# EASYEDA_SCHEMA.net
KiCad netlist of a schematic drawn in EasyEDA
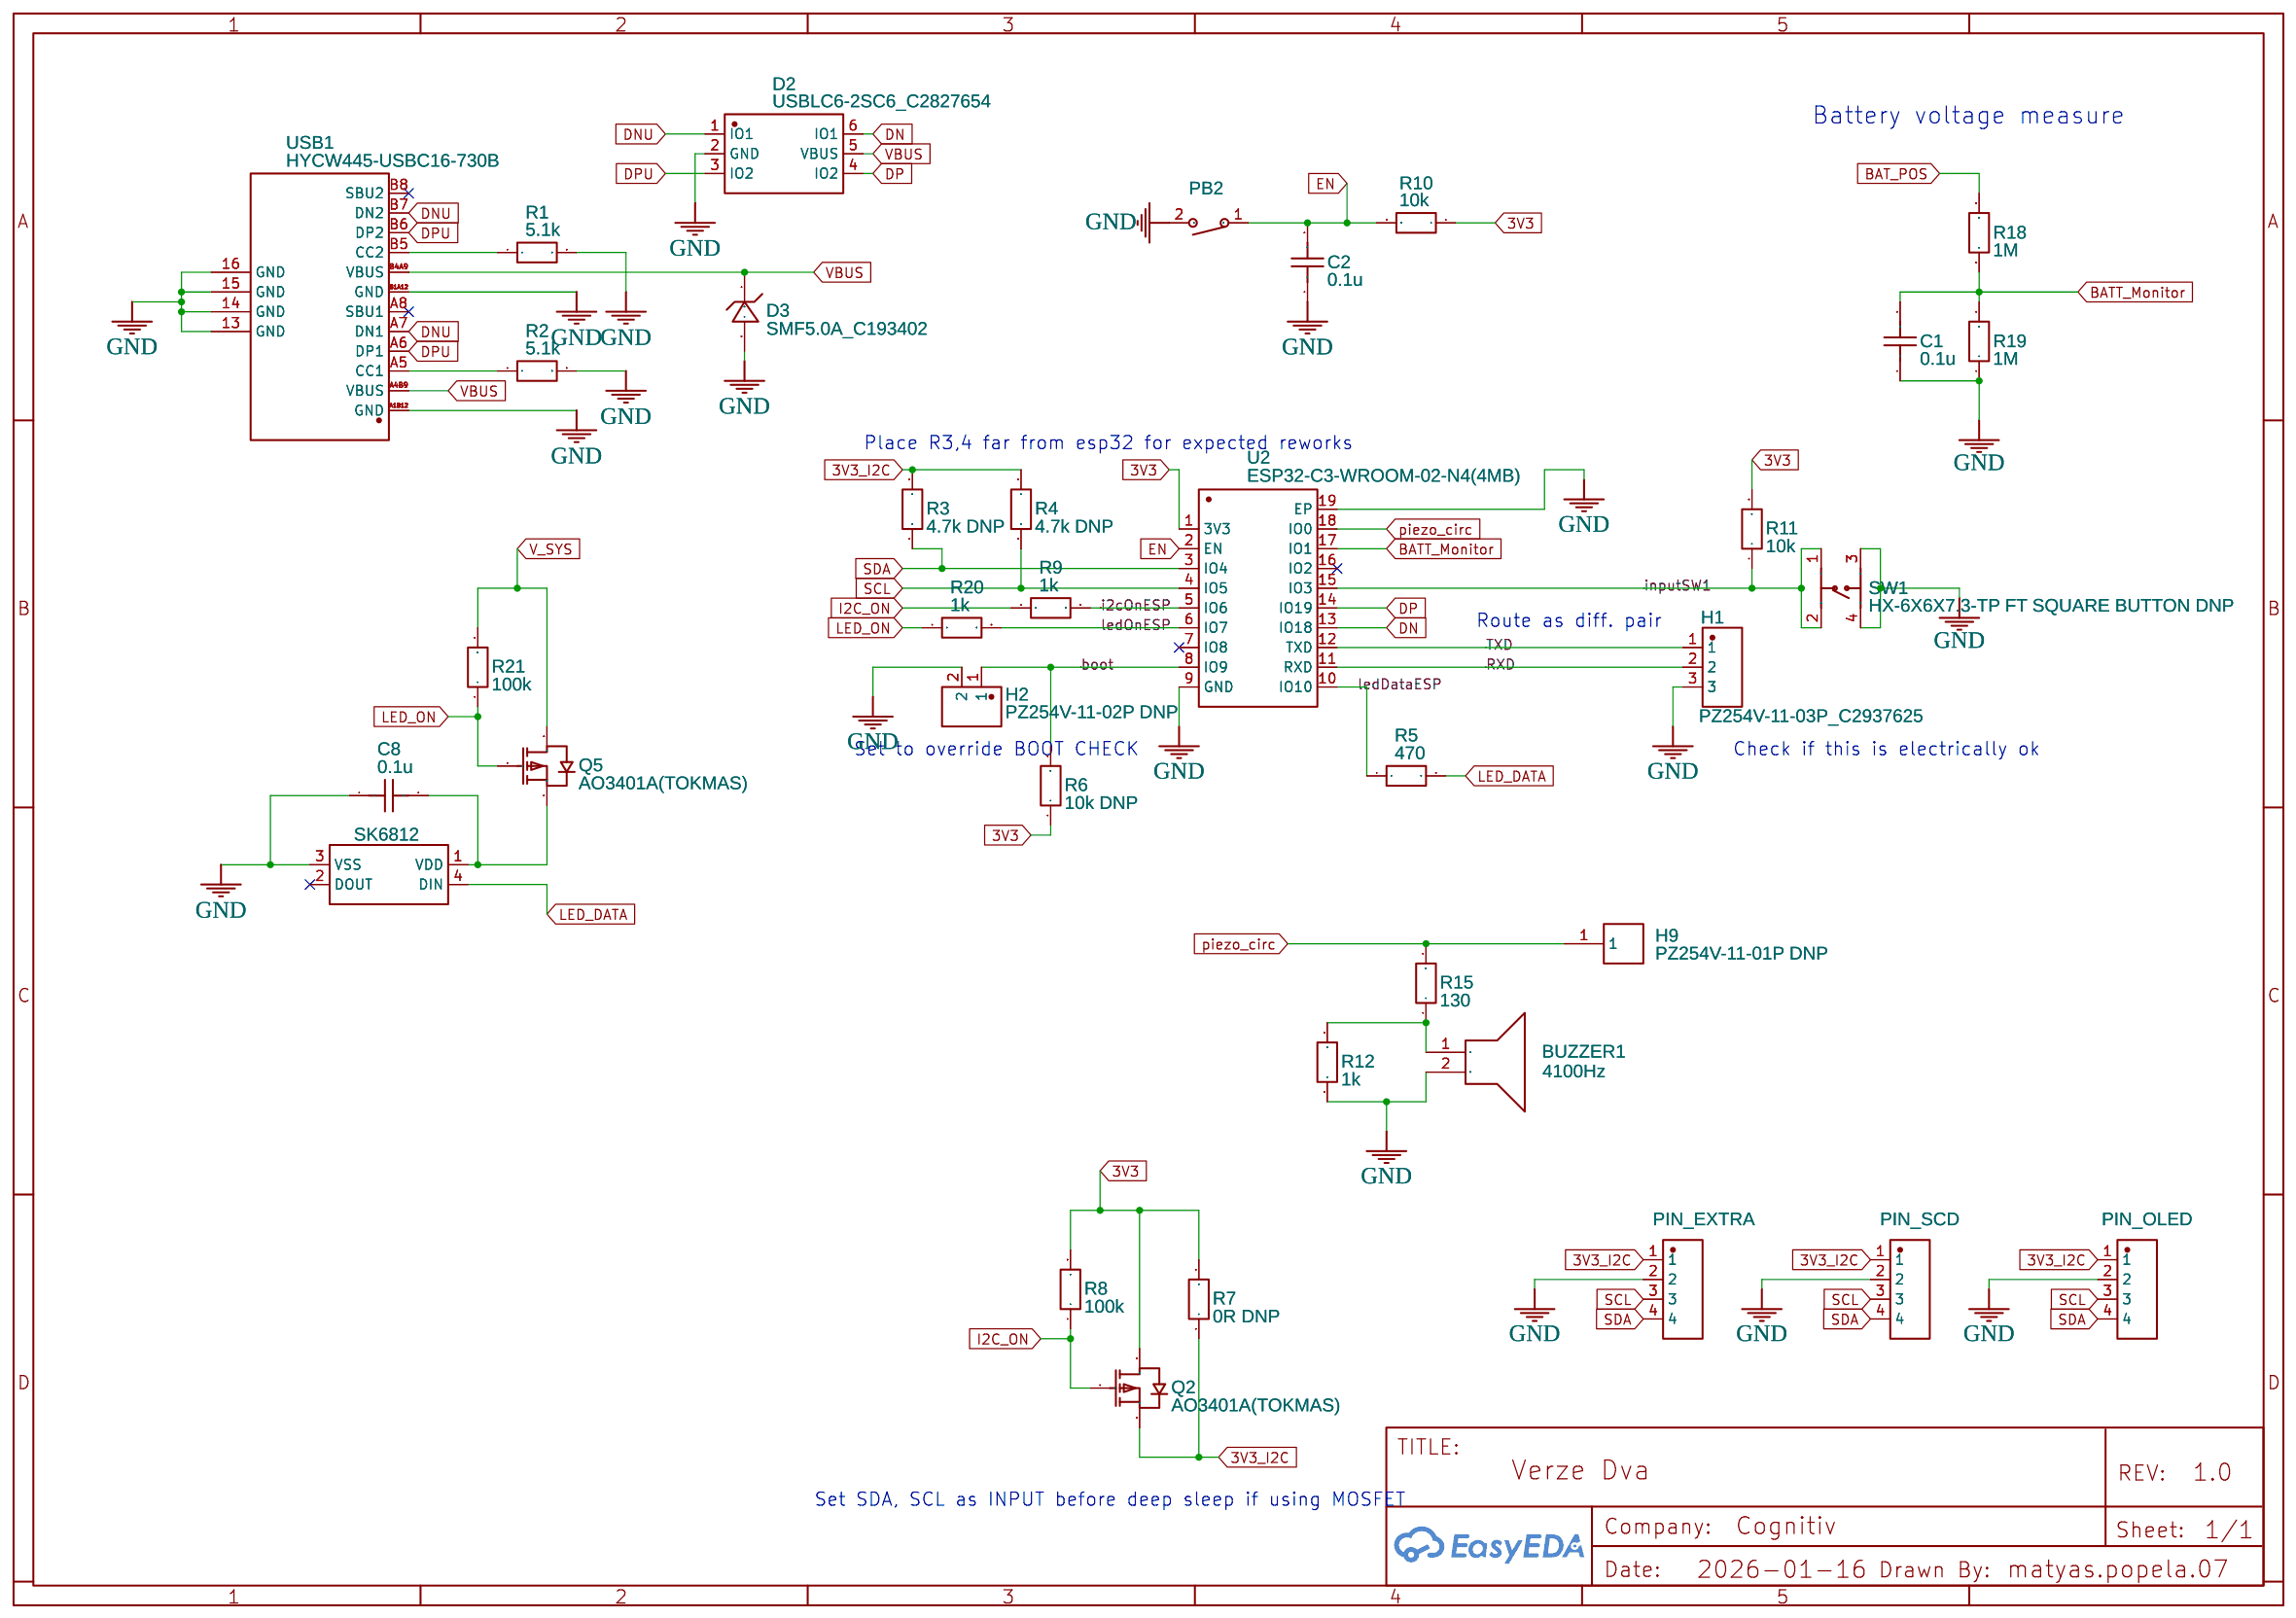
[diagram p0: Mainboard_C3]
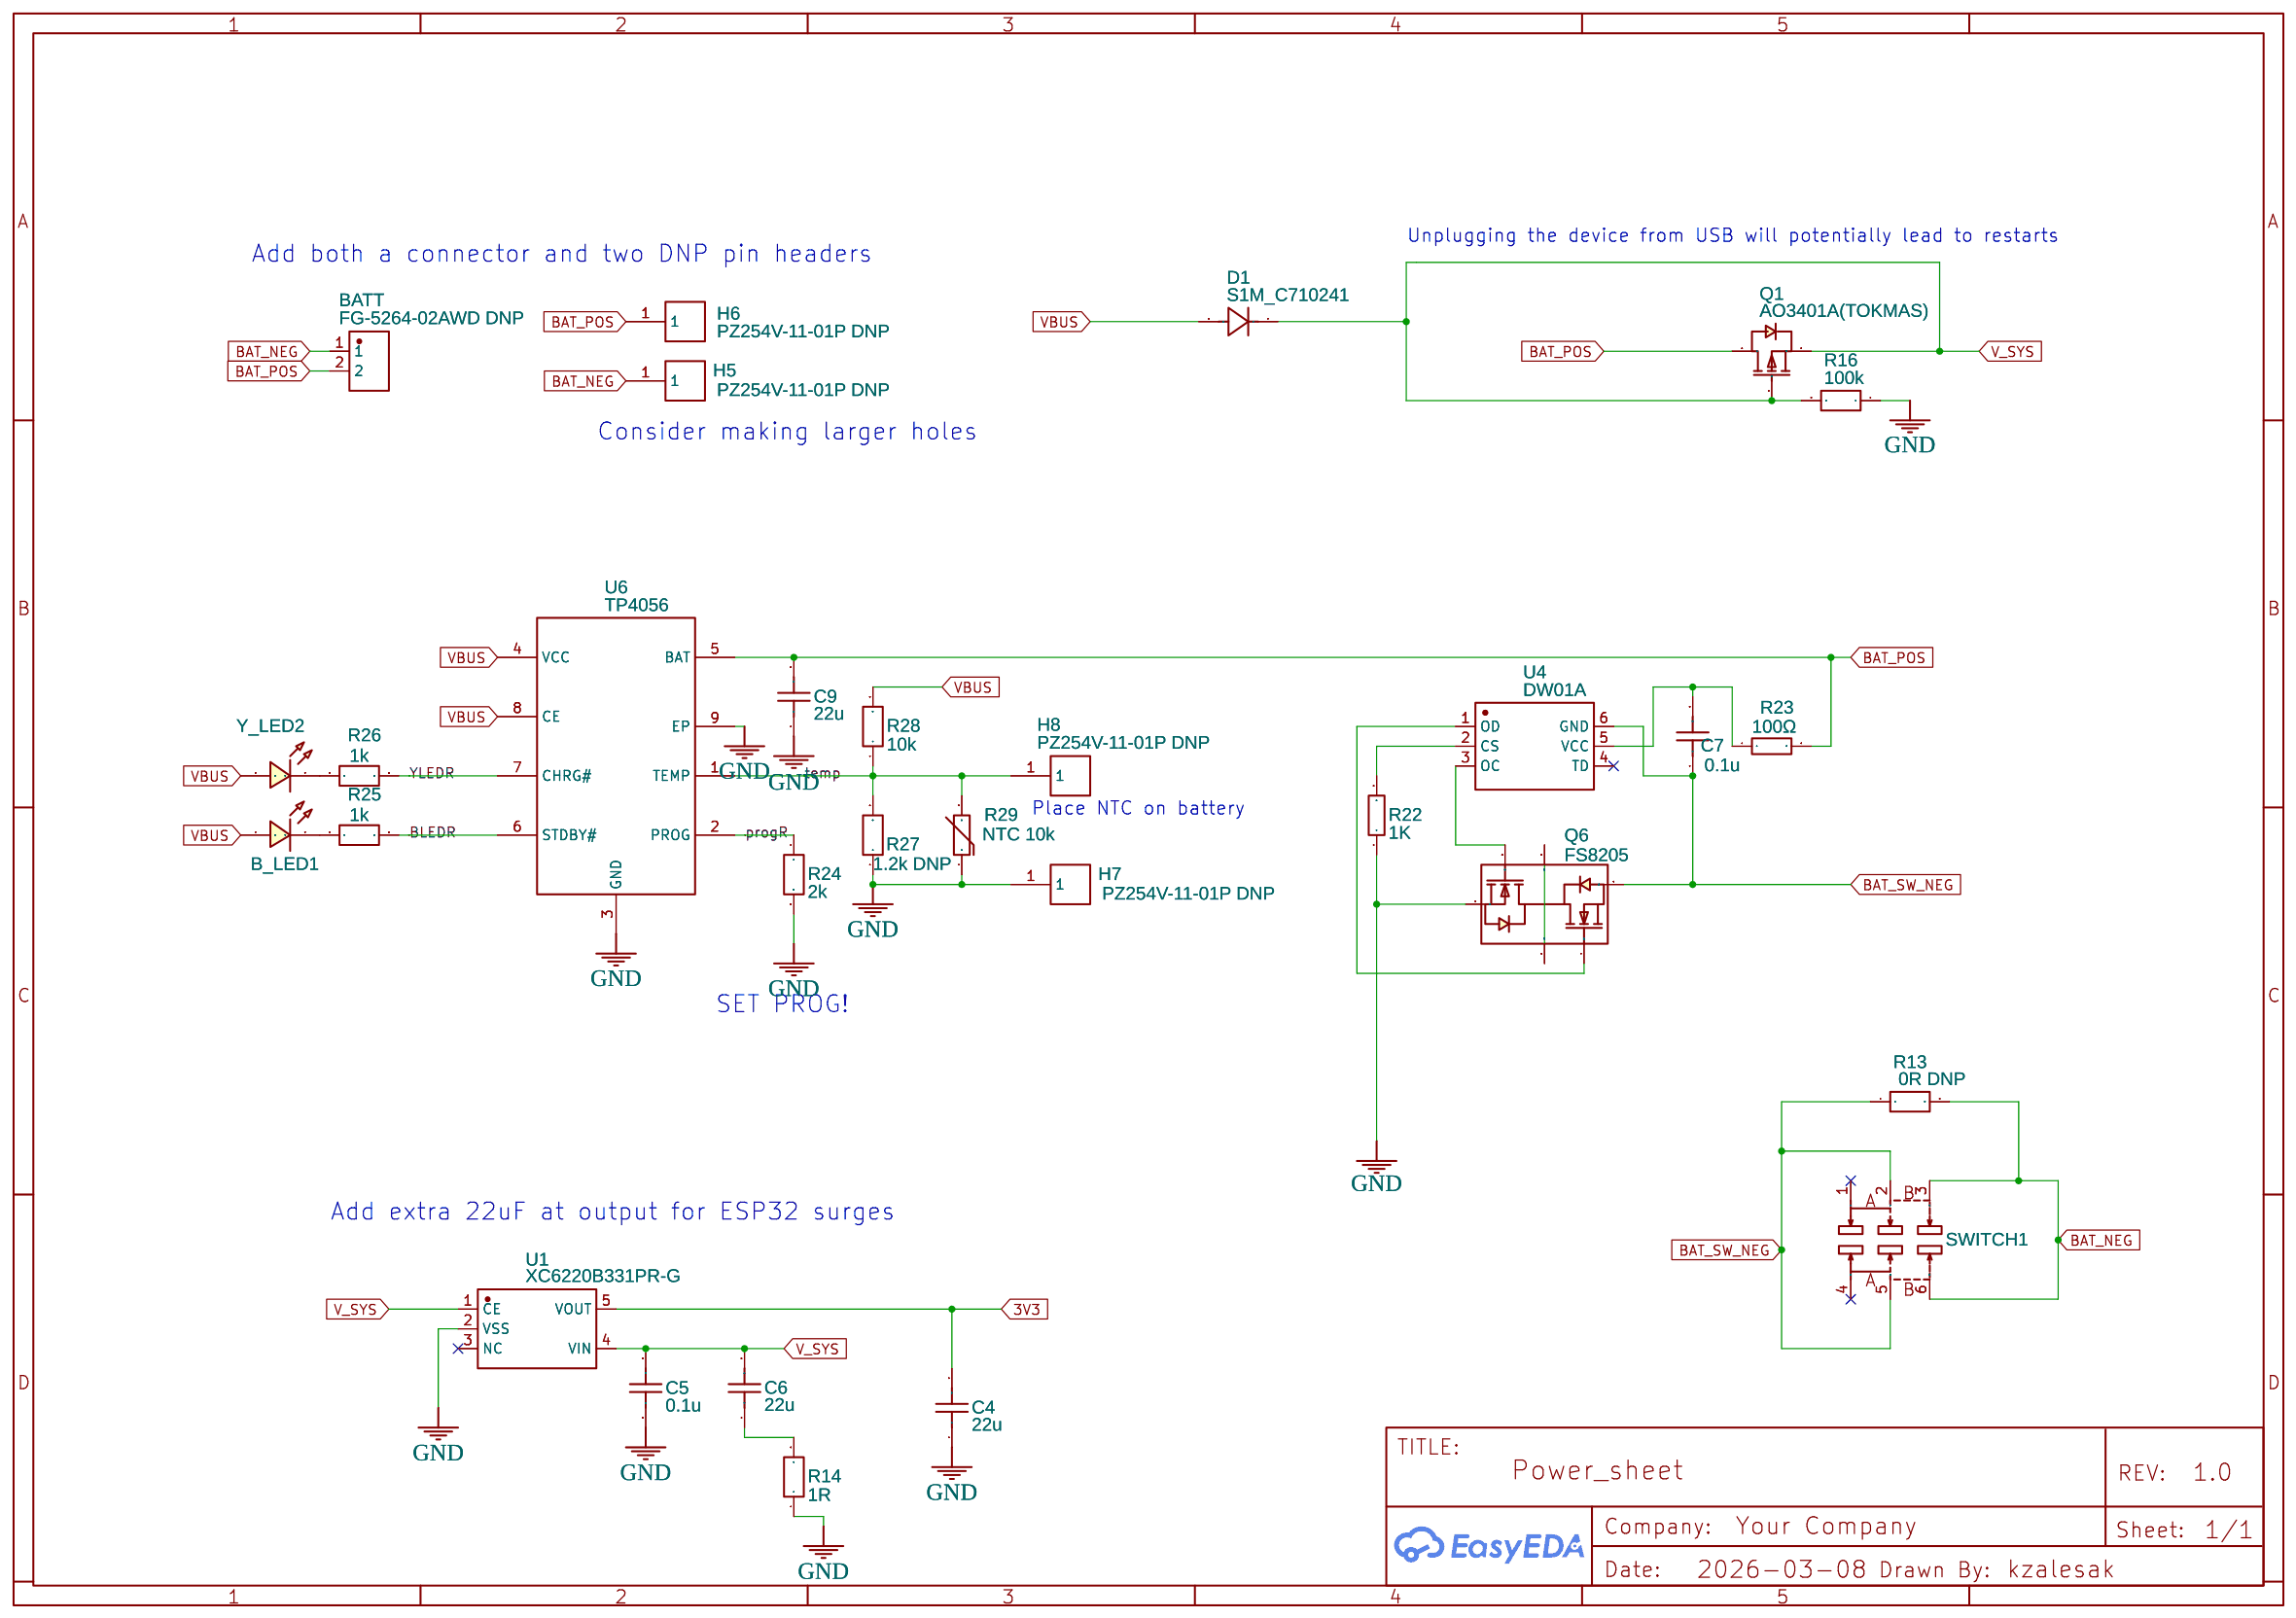
[diagram p1: Power_Management]

(export (version "E")
  (design (tool "Eeschema 10.0.6"))
  (components
    (comp (ref "BUZZER1")
      (value "4100Hz")
      (fields (field (name "Manufacturer Part") "FUET-1109") (field (name "Manufacturer") "FUET(福声科技)"))
      (libsource (lib "") (part "FST-1109"))
    )
    (comp (ref "C1")
      (value "0.1u")
      (fields
        (field (name "Manufacturer Part") "CC0603KRX7R9BB104")
        (field (name "Manufacturer") "YAGEO(国巨)")
      )
      (libsource (lib "") (part "C_0603_US"))
    )
    (comp (ref "C2")
      (value "0.1u")
      (fields
        (field (name "Manufacturer Part") "CC0603KRX7R9BB104")
        (field (name "Manufacturer") "YAGEO(国巨)")
      )
      (libsource (lib "") (part "C_0603_US"))
    )
    (comp (ref "C8")
      (value "0.1u")
      (fields
        (field (name "Manufacturer Part") "CC0603KRX7R9BB104")
        (field (name "Manufacturer") "YAGEO(国巨)")
      )
      (libsource (lib "") (part "C_0603_US_1"))
    )
    (comp (ref "D2")
      (value "USBLC6-2SC6_C2827654")
      (fields
        (field (name "Manufacturer Part") "USBLC6-2SC6")
        (field (name "Manufacturer") "TECH PUBLIC(台舟)")
      )
      (libsource (lib "") (part "USBLC6-2SC6_C2827654"))
    )
    (comp (ref "D3")
      (value "SMF5.0A_C193402")
      (fields (field (name "Manufacturer Part") "SMF5.0A") (field (name "Manufacturer") "MDD(辰达半导体)"))
      (libsource (lib "") (part "SMF5.0A_C193402"))
    )
    (comp (ref "H1")
      (value "PZ254V-11-03P_C2937625")
      (fields (field (name "Manufacturer Part") "PZ254V-11-03P") (field (name "Manufacturer") "XFCN(兴飞)"))
      (libsource (lib "") (part "PZ254V-11-03P_C2937625"))
    )
    (comp (ref "H2")
      (value "PZ254V-11-02P DNP")
      (fields (field (name "Manufacturer Part") "PZ254V-11-02P") (field (name "Manufacturer") "XFCN(兴飞)"))
      (libsource (lib "") (part "PZ254V-11-02P"))
    )
    (comp (ref "H9")
      (value "PZ254V-11-01P DNP")
      (fields (field (name "Manufacturer Part") "PZ254V-11-01P") (field (name "Manufacturer") "XFCN(兴飞)"))
      (libsource (lib "") (part "PZ254V-11-01P"))
    )
    (comp (ref "PB2")
      (value "HX 3X4X2-2P-1.6N TACTILE SWITCH DNP")
      (fields
        (field (name "Manufacturer Part") "HX 3x4x2-2P-1.6N TACTILE SWITCH")
        (field (name "Manufacturer") "hanxia(韩下)")
      )
      (libsource (lib "") (part "HX 3X4X2-2P-1.6N TACTILE SWITCH"))
    )
    (comp (ref "PIN_EXTRA")
      (value "2.54-1*4")
      (fields (field (name "Manufacturer") "ZHOURI(洲日)"))
      (libsource (lib "") (part "2.54-1*4"))
    )
    (comp (ref "PIN_OLED")
      (value "2.54-1*4")
      (fields (field (name "Manufacturer") "ZHOURI(洲日)"))
      (libsource (lib "") (part "2.54-1*4_2"))
    )
    (comp (ref "PIN_SCD")
      (value "2.54-1*4")
      (fields (field (name "Manufacturer") "ZHOURI(洲日)"))
      (libsource (lib "") (part "2.54-1*4_1"))
    )
    (comp (ref "Q2")
      (value "AO3401A(TOKMAS)")
      (fields (field (name "Manufacturer") "Tokmas(托克马斯)"))
      (libsource (lib "") (part "AO3401A(TOKMAS)"))
    )
    (comp (ref "Q5")
      (value "AO3401A(TOKMAS)")
      (fields (field (name "Manufacturer") "Tokmas(托克马斯)"))
      (libsource (lib "") (part "AO3401A(TOKMAS)"))
    )
    (comp (ref "R1")
      (value "5.1k")
      (fields
        (field (name "Manufacturer Part") "0603WAF5101T5E")
        (field (name "Manufacturer") "UNI-ROYAL(厚声)")
      )
      (libsource (lib "") (part "R_0603_EU"))
    )
    (comp (ref "R2")
      (value "5.1k")
      (fields
        (field (name "Manufacturer Part") "0603WAF5101T5E")
        (field (name "Manufacturer") "UNI-ROYAL(厚声)")
      )
      (libsource (lib "") (part "R_0603_EU"))
    )
    (comp (ref "R3")
      (value "4.7k DNP")
      (fields
        (field (name "Manufacturer Part") "0603WAF4701T5E")
        (field (name "Manufacturer") "UNI-ROYAL(厚声)")
      )
      (libsource (lib "") (part "R_0603_EU_2"))
    )
    (comp (ref "R4")
      (value "4.7k DNP")
      (fields
        (field (name "Manufacturer Part") "0603WAF4701T5E")
        (field (name "Manufacturer") "UNI-ROYAL(厚声)")
      )
      (libsource (lib "") (part "R_0603_EU_2"))
    )
    (comp (ref "R5")
      (value "470")
      (fields
        (field (name "Manufacturer Part") "0603WAF4700T5E")
        (field (name "Manufacturer") "UNI-ROYAL(厚声)")
      )
      (libsource (lib "") (part "R_0603_EU"))
    )
    (comp (ref "R6")
      (value "10k DNP")
      (fields
        (field (name "Manufacturer Part") "0603WAF1002T5E")
        (field (name "Manufacturer") "UNI-ROYAL(厚声)")
      )
      (libsource (lib "") (part "R_0603_EU_2"))
    )
    (comp (ref "R7")
      (value "0R DNP")
      (fields
        (field (name "Manufacturer Part") "0603WAF0000T5E")
        (field (name "Manufacturer") "UNI-ROYAL(厚声)")
      )
      (libsource (lib "") (part "R_0603_EU_2"))
    )
    (comp (ref "R8")
      (value "100k")
      (fields
        (field (name "Manufacturer Part") "0603WAF1003T5E")
        (field (name "Manufacturer") "UNI-ROYAL(厚声)")
      )
      (libsource (lib "") (part "R_0603_EU_2"))
    )
    (comp (ref "R9")
      (value "1k")
      (fields
        (field (name "Manufacturer Part") "0603WAF1001T5E")
        (field (name "Manufacturer") "UNI-ROYAL(厚声)")
      )
      (libsource (lib "") (part "R_0603_EU"))
    )
    (comp (ref "R10")
      (value "10k")
      (fields
        (field (name "Manufacturer Part") "0603WAF1002T5E")
        (field (name "Manufacturer") "UNI-ROYAL(厚声)")
      )
      (libsource (lib "") (part "R_0603_EU_1"))
    )
    (comp (ref "R11")
      (value "10k")
      (fields
        (field (name "Manufacturer Part") "0603WAF1002T5E")
        (field (name "Manufacturer") "UNI-ROYAL(厚声)")
      )
      (libsource (lib "") (part "R_0603_EU_2"))
    )
    (comp (ref "R12")
      (value "1k")
      (fields
        (field (name "Manufacturer Part") "0603WAF1001T5E")
        (field (name "Manufacturer") "UNI-ROYAL(厚声)")
      )
      (libsource (lib "") (part "R_0603_EU_2"))
    )
    (comp (ref "R15")
      (value "130")
      (fields
        (field (name "Manufacturer Part") "0603WAF1200T5E")
        (field (name "Manufacturer") "UNI-ROYAL(厚声)")
      )
      (libsource (lib "") (part "R_0603_EU_2"))
    )
    (comp (ref "R18")
      (value "1M")
      (fields
        (field (name "Manufacturer Part") "0603WAF1004T5E")
        (field (name "Manufacturer") "UNI-ROYAL(厚声)")
      )
      (libsource (lib "") (part "R_0603_EU_2"))
    )
    (comp (ref "R19")
      (value "1M")
      (fields
        (field (name "Manufacturer Part") "0603WAF1004T5E")
        (field (name "Manufacturer") "UNI-ROYAL(厚声)")
      )
      (libsource (lib "") (part "R_0603_EU_2"))
    )
    (comp (ref "R20")
      (value "1k")
      (fields
        (field (name "Manufacturer Part") "0603WAF1001T5E")
        (field (name "Manufacturer") "UNI-ROYAL(厚声)")
      )
      (libsource (lib "") (part "R_0603_EU"))
    )
    (comp (ref "R21")
      (value "100k")
      (fields
        (field (name "Manufacturer Part") "0603WAF1003T5E")
        (field (name "Manufacturer") "UNI-ROYAL(厚声)")
      )
      (libsource (lib "") (part "R_0603_EU_2"))
    )
    (comp (ref "SK6812")
      (value "SK6812_C5378720")
      (fields (field (name "Manufacturer Part") "SK6812") (field (name "Manufacturer") "欧思科光电"))
      (libsource (lib "") (part "SK6812_C5378720"))
    )
    (comp (ref "SW1")
      (value "HX-6X6X7.3-TP FT SQUARE BUTTON DNP")
      (fields
        (field (name "Manufacturer Part") "HX-6x6x7.3-TP FT square button")
        (field (name "Manufacturer") "hanxia(韩下)")
      )
      (libsource (lib "") (part "HX-6X6X7.3-TP FT SQUARE BUTTON"))
    )
    (comp (ref "U2")
      (value "ESP32-C3-WROOM-02-N4(4MB)")
      (fields
        (field (name "Manufacturer Part") "ESP32-C3-WROOM-02-N4")
        (field (name "Manufacturer") "ESPRESSIF(乐鑫)")
      )
      (libsource (lib "") (part "ESP32-C3-WROOM-02-N4(4MB)"))
    )
    (comp (ref "USB1")
      (value "HYCW445-USBC16-730B")
      (fields (field (name "Manufacturer") "华宇创"))
      (libsource (lib "") (part "HYCW445-USBC16-730B"))
    )
    (comp (ref "BATT")
      (value "FG-5264-02AWD DNP")
      (fields (field (name "Manufacturer Part") "FG-5264-02AWD") (field (name "Manufacturer") "FG(富港)"))
      (libsource (lib "") (part "FG-5264-02AWD"))
    )
    (comp (ref "B_LED1")
      (value "LED-0603_R")
      (fields
        (field (name "Manufacturer Part") "19-217/R6C-AL1M2VY/3T")
        (field (name "Manufacturer") "EVERLIGHT(台湾亿光)")
      )
      (libsource (lib "") (part "LED-0603_R"))
    )
    (comp (ref "C4")
      (value "22u")
      (fields
        (field (name "Manufacturer Part") "CL21A226MAQNNNE")
        (field (name "Manufacturer") "SAMSUNG(三星)")
      )
      (libsource (lib "") (part "CL21A226MAQNNNE"))
    )
    (comp (ref "C5")
      (value "0.1u")
      (fields
        (field (name "Manufacturer Part") "CC0603KRX7R9BB104")
        (field (name "Manufacturer") "YAGEO(国巨)")
      )
      (libsource (lib "") (part "C_0603_US"))
    )
    (comp (ref "C6")
      (value "22u")
      (fields
        (field (name "Manufacturer Part") "CL21A226MAQNNNE")
        (field (name "Manufacturer") "SAMSUNG(三星)")
      )
      (libsource (lib "") (part "CL21A226MAQNNNE"))
    )
    (comp (ref "C7")
      (value "0.1u")
      (fields
        (field (name "Manufacturer Part") "CC0603KRX7R9BB104")
        (field (name "Manufacturer") "YAGEO(国巨)")
      )
      (libsource (lib "") (part "C_0603_US"))
    )
    (comp (ref "C9")
      (value "22u")
      (fields
        (field (name "Manufacturer Part") "CL21A226MAQNNNE")
        (field (name "Manufacturer") "SAMSUNG(三星)")
      )
      (libsource (lib "") (part "CL21A226MAQNNNE"))
    )
    (comp (ref "D1")
      (value "S1M_C710241")
      (fields (field (name "Manufacturer Part") "S1M") (field (name "Manufacturer") "DIODES(美台)"))
      (libsource (lib "") (part "S1M_C710241"))
    )
    (comp (ref "H5")
      (value "PZ254V-11-01P DNP")
      (fields (field (name "Manufacturer Part") "PZ254V-11-01P") (field (name "Manufacturer") "XFCN(兴飞)"))
      (libsource (lib "") (part "PZ254V-11-01P"))
    )
    (comp (ref "H6")
      (value "PZ254V-11-01P DNP")
      (fields (field (name "Manufacturer Part") "PZ254V-11-01P") (field (name "Manufacturer") "XFCN(兴飞)"))
      (libsource (lib "") (part "PZ254V-11-01P"))
    )
    (comp (ref "H7")
      (value "PZ254V-11-01P DNP")
      (fields (field (name "Manufacturer Part") "PZ254V-11-01P") (field (name "Manufacturer") "XFCN(兴飞)"))
      (libsource (lib "") (part "PZ254V-11-01P"))
    )
    (comp (ref "H8")
      (value "PZ254V-11-01P DNP")
      (fields (field (name "Manufacturer Part") "PZ254V-11-01P") (field (name "Manufacturer") "XFCN(兴飞)"))
      (libsource (lib "") (part "PZ254V-11-01P"))
    )
    (comp (ref "Q1")
      (value "AO3401A(TOKMAS)")
      (fields (field (name "Manufacturer") "Tokmas(托克马斯)"))
      (libsource (lib "") (part "AO3401A(TOKMAS)"))
    )
    (comp (ref "Q6")
      (value "FS8205")
      (fields (field (name "Manufacturer") "FORTUNE"))
      (libsource (lib "") (part "Unknown_775_-355"))
    )
    (comp (ref "R13")
      (value "0R DNP")
      (fields
        (field (name "Manufacturer Part") "0805W8F0000T5E")
        (field (name "Manufacturer") "UNI-ROYAL(厚声)")
      )
      (libsource (lib "") (part "R_0603_EU"))
    )
    (comp (ref "R14")
      (value "1R")
      (fields
        (field (name "Manufacturer Part") "0603WAF100KT5E")
        (field (name "Manufacturer") "UNI-ROYAL(厚声)")
      )
      (libsource (lib "") (part "R_0603_EU_3"))
    )
    (comp (ref "R16")
      (value "100k")
      (fields
        (field (name "Manufacturer Part") "0603WAF1003T5E")
        (field (name "Manufacturer") "UNI-ROYAL(厚声)")
      )
      (libsource (lib "") (part "R_0603_EU_1"))
    )
    (comp (ref "R22")
      (value "1K")
      (fields (field (name "Manufacturer Part") "ERJ3GEYJ102V") (field (name "Manufacturer") "PANASONIC"))
      (libsource (lib "") (part "ERJ3GEYJ102V"))
    )
    (comp (ref "R23")
      (value "100Ω")
      (fields (field (name "Manufacturer Part") "0603WAJ0101T5E") (field (name "Manufacturer") "UniOhm"))
      (libsource (lib "") (part "0603WAJ0101T5E"))
    )
    (comp (ref "R24")
      (value "2k")
      (fields
        (field (name "Manufacturer Part") "0805W8F2001T5E")
        (field (name "Manufacturer") "UNI-ROYAL(厚声)")
      )
      (libsource (lib "") (part "R_0603_EU_2"))
    )
    (comp (ref "R25")
      (value "1k")
      (fields
        (field (name "Manufacturer Part") "0603WAF1001T5E")
        (field (name "Manufacturer") "UNI-ROYAL(厚声)")
      )
      (libsource (lib "") (part "R_0603_EU"))
    )
    (comp (ref "R26")
      (value "1k")
      (fields
        (field (name "Manufacturer Part") "0603WAF1001T5E")
        (field (name "Manufacturer") "UNI-ROYAL(厚声)")
      )
      (libsource (lib "") (part "R_0603_EU"))
    )
    (comp (ref "R27")
      (value "1.2k DNP")
      (fields
        (field (name "Manufacturer Part") "0603WAF1201T5E")
        (field (name "Manufacturer") "UNI-ROYAL(厚声)")
      )
      (libsource (lib "") (part "R_0603_EU_3"))
    )
    (comp (ref "R28")
      (value "10k")
      (fields
        (field (name "Manufacturer Part") "0603WAF1002T5E")
        (field (name "Manufacturer") "UNI-ROYAL(厚声)")
      )
      (libsource (lib "") (part "R_0603_EU_3"))
    )
    (comp (ref "R29")
      (value "NTC 10k")
      (fields (field (name "Manufacturer Part") "CMFB103F3950FANT") (field (name "Manufacturer") "FH(风华)"))
      (libsource (lib "") (part "CMFB103F3950FANT"))
    )
    (comp (ref "SWITCH1")
      (value "MST22D18G2 125 DNP")
      (fields
        (field (name "Manufacturer Part") "MST22D18G2 125")
        (field (name "Manufacturer") "SHOU HAN(首韩)")
      )
      (libsource (lib "") (part "MST22D18G2 125"))
    )
    (comp (ref "U1")
      (value "XC6220B331PR-G")
      (fields (field (name "Manufacturer") "TOREX(特瑞仕)"))
      (libsource (lib "") (part "XC6220B331PR-G"))
    )
    (comp (ref "U4")
      (value "DW01A")
      (fields (field (name "Manufacturer") "PUOLOP"))
      (libsource (lib "") (part "Unknown_770_-435"))
    )
    (comp (ref "U6")
      (value "TP4056")
      (fields
        (field (name "Manufacturer Part") "TP4056-42-ESOP8")
        (field (name "Manufacturer") "TOPPOWER(南京拓微)")
      )
      (libsource (lib "") (part "TP4056"))
    )
    (comp (ref "Y_LED2")
      (value "LED-0603_R")
      (fields
        (field (name "Manufacturer Part") "19-217/R6C-AL1M2VY/3T")
        (field (name "Manufacturer") "EVERLIGHT(台湾亿光)")
      )
      (libsource (lib "") (part "LED-0603_R_1"))
    )
  )
  (nets
    (net (code "1") (name "3V3") (class "Default")
      (node (ref "C4") (pin "2") (pinfunction "2_2") (pintype "unspecified"))
      (node (ref "Q2") (pin "3") (pinfunction "D_3") (pintype "unspecified"))
      (node (ref "R10") (pin "1") (pinfunction "1_1") (pintype "unspecified"))
      (node (ref "R11") (pin "2") (pinfunction "2_2") (pintype "unspecified"))
      (node (ref "R6") (pin "1") (pinfunction "1_1") (pintype "unspecified"))
      (node (ref "R7") (pin "2") (pinfunction "2_2") (pintype "unspecified"))
      (node (ref "R8") (pin "2") (pinfunction "2_2") (pintype "unspecified"))
      (node (ref "U1") (pin "5") (pinfunction "VOUT_5") (pintype "unspecified"))
      (node (ref "U2") (pin "1") (pinfunction "3V3_1") (pintype "unspecified"))
    )
    (net (code "2") (name "3V3_I2C") (class "Default")
      (node (ref "PIN_EXTRA") (pin "1") (pinfunction "1_1") (pintype "unspecified"))
      (node (ref "PIN_OLED") (pin "1") (pinfunction "1_1") (pintype "unspecified"))
      (node (ref "PIN_SCD") (pin "1") (pinfunction "1_1") (pintype "unspecified"))
      (node (ref "Q2") (pin "2") (pinfunction "S_2") (pintype "unspecified"))
      (node (ref "R3") (pin "2") (pinfunction "2_2") (pintype "unspecified"))
      (node (ref "R4") (pin "2") (pinfunction "2_2") (pintype "unspecified"))
      (node (ref "R7") (pin "1") (pinfunction "1_1") (pintype "unspecified"))
    )
    (net (code "3") (name "BATT_Monitor") (class "Default")
      (node (ref "C1") (pin "2") (pinfunction "2_2") (pintype "unspecified"))
      (node (ref "R18") (pin "1") (pinfunction "1_1") (pintype "unspecified"))
      (node (ref "R19") (pin "2") (pinfunction "2_2") (pintype "unspecified"))
      (node (ref "U2") (pin "17") (pinfunction "IO1_17") (pintype "unspecified"))
    )
    (net (code "4") (name "BAT_NEG") (class "Default")
      (node (ref "BATT") (pin "1") (pinfunction "1_1") (pintype "unspecified"))
      (node (ref "H5") (pin "1") (pinfunction "1_1") (pintype "unspecified"))
      (node (ref "R13") (pin "2") (pinfunction "2_2") (pintype "unspecified"))
      (node (ref "SWITCH1") (pin "3") (pinfunction "3_3") (pintype "unspecified"))
      (node (ref "SWITCH1") (pin "6") (pinfunction "6_6") (pintype "unspecified"))
    )
    (net (code "5") (name "BAT_POS") (class "Default")
      (node (ref "BATT") (pin "2") (pinfunction "2_2") (pintype "unspecified"))
      (node (ref "C9") (pin "2") (pinfunction "2_2") (pintype "unspecified"))
      (node (ref "H6") (pin "1") (pinfunction "1_1") (pintype "unspecified"))
      (node (ref "Q1") (pin "3") (pinfunction "D_3") (pintype "unspecified"))
      (node (ref "R18") (pin "2") (pinfunction "2_2") (pintype "unspecified"))
      (node (ref "R23") (pin "2") (pinfunction "2_2") (pintype "input"))
      (node (ref "U6") (pin "5") (pinfunction "BAT_5") (pintype "unspecified"))
    )
    (net (code "6") (name "BAT_SW_NEG") (class "Default")
      (node (ref "C7") (pin "1") (pinfunction "1_1") (pintype "unspecified"))
      (node (ref "Q6") (pin "3") (pinfunction "S2_3") (pintype "unspecified"))
      (node (ref "R13") (pin "1") (pinfunction "1_1") (pintype "unspecified"))
      (node (ref "SWITCH1") (pin "2") (pinfunction "2_2") (pintype "unspecified"))
      (node (ref "SWITCH1") (pin "5") (pinfunction "5_5") (pintype "unspecified"))
      (node (ref "U4") (pin "6") (pinfunction "GND_6") (pintype "unspecified"))
    )
    (net (code "7") (name "BLEDR") (class "Default")
      (node (ref "R25") (pin "2") (pinfunction "2_2") (pintype "unspecified"))
      (node (ref "U6") (pin "6") (pinfunction "STDBY#_6") (pintype "unspecified"))
    )
    (net (code "8") (name "DN") (class "Default")
      (node (ref "D2") (pin "6") (pinfunction "IO1_6") (pintype "unspecified"))
      (node (ref "U2") (pin "13") (pinfunction "IO18_13") (pintype "unspecified"))
    )
    (net (code "9") (name "DNU") (class "Default")
      (node (ref "D2") (pin "1") (pinfunction "IO1_1") (pintype "unspecified"))
      (node (ref "USB1") (pin "A7") (pinfunction "DN1_A7") (pintype "unspecified"))
      (node (ref "USB1") (pin "B7") (pinfunction "DN2_B7") (pintype "unspecified"))
    )
    (net (code "10") (name "DP") (class "Default")
      (node (ref "D2") (pin "4") (pinfunction "IO2_4") (pintype "unspecified"))
      (node (ref "U2") (pin "14") (pinfunction "IO19_14") (pintype "unspecified"))
    )
    (net (code "11") (name "DPU") (class "Default")
      (node (ref "D2") (pin "3") (pinfunction "IO2_3") (pintype "unspecified"))
      (node (ref "USB1") (pin "A6") (pinfunction "DP1_A6") (pintype "unspecified"))
      (node (ref "USB1") (pin "B6") (pinfunction "DP2_B6") (pintype "unspecified"))
    )
    (net (code "12") (name "EN") (class "Default")
      (node (ref "C2") (pin "2") (pinfunction "2_2") (pintype "unspecified"))
      (node (ref "PB2") (pin "1") (pinfunction "1_1") (pintype "unspecified"))
      (node (ref "R10") (pin "2") (pinfunction "2_2") (pintype "unspecified"))
      (node (ref "U2") (pin "2") (pinfunction "EN_2") (pintype "unspecified"))
    )
    (net (code "13") (name "GND") (class "Default")
      (node (ref "BUZZER1") (pin "2") (pinfunction "2_2") (pintype "unspecified"))
      (node (ref "C1") (pin "1") (pinfunction "1_1") (pintype "unspecified"))
      (node (ref "C2") (pin "1") (pinfunction "1_1") (pintype "unspecified"))
      (node (ref "C4") (pin "1") (pinfunction "1_1") (pintype "unspecified"))
      (node (ref "C5") (pin "1") (pinfunction "1_1") (pintype "unspecified"))
      (node (ref "C8") (pin "1") (pinfunction "1_1") (pintype "unspecified"))
      (node (ref "C9") (pin "1") (pinfunction "1_1") (pintype "unspecified"))
      (node (ref "D2") (pin "2") (pinfunction "GND_2") (pintype "unspecified"))
      (node (ref "D3") (pin "2") (pinfunction "A_2") (pintype "unspecified"))
      (node (ref "H1") (pin "3") (pinfunction "3_3") (pintype "unspecified"))
      (node (ref "H2") (pin "2") (pinfunction "2_2") (pintype "unspecified"))
      (node (ref "H7") (pin "1") (pinfunction "1_1") (pintype "unspecified"))
      (node (ref "PB2") (pin "2") (pinfunction "2_2") (pintype "unspecified"))
      (node (ref "PIN_EXTRA") (pin "2") (pinfunction "2_2") (pintype "unspecified"))
      (node (ref "PIN_OLED") (pin "2") (pinfunction "2_2") (pintype "unspecified"))
      (node (ref "PIN_SCD") (pin "2") (pinfunction "2_2") (pintype "unspecified"))
      (node (ref "Q6") (pin "1") (pinfunction "S1_1") (pintype "unspecified"))
      (node (ref "R1") (pin "2") (pinfunction "2_2") (pintype "unspecified"))
      (node (ref "R12") (pin "1") (pinfunction "1_1") (pintype "unspecified"))
      (node (ref "R14") (pin "1") (pinfunction "1_1") (pintype "unspecified"))
      (node (ref "R16") (pin "1") (pinfunction "1_1") (pintype "unspecified"))
      (node (ref "R19") (pin "1") (pinfunction "1_1") (pintype "unspecified"))
      (node (ref "R2") (pin "2") (pinfunction "2_2") (pintype "unspecified"))
      (node (ref "R22") (pin "1") (pinfunction "1_1") (pintype "unspecified"))
      (node (ref "R24") (pin "2") (pinfunction "2_2") (pintype "unspecified"))
      (node (ref "R27") (pin "1") (pinfunction "1_1") (pintype "unspecified"))
      (node (ref "R29") (pin "1") (pinfunction "1_1") (pintype "input"))
      (node (ref "SK6812") (pin "3") (pinfunction "VSS_3") (pintype "unspecified"))
      (node (ref "SW1") (pin "3") (pinfunction "C_3") (pintype "unspecified"))
      (node (ref "SW1") (pin "4") (pinfunction "D_4") (pintype "unspecified"))
      (node (ref "U1") (pin "2") (pinfunction "VSS_2") (pintype "unspecified"))
      (node (ref "U2") (pin "19") (pinfunction "EP_19") (pintype "unspecified"))
      (node (ref "U2") (pin "9") (pinfunction "GND_9") (pintype "unspecified"))
      (node (ref "U6") (pin "3") (pinfunction "GND_3") (pintype "unspecified"))
      (node (ref "U6") (pin "9") (pinfunction "EP_9") (pintype "unspecified"))
      (node (ref "USB1") (pin "13") (pinfunction "GND_13") (pintype "unspecified"))
      (node (ref "USB1") (pin "14") (pinfunction "GND_14") (pintype "unspecified"))
      (node (ref "USB1") (pin "15") (pinfunction "GND_15") (pintype "unspecified"))
      (node (ref "USB1") (pin "16") (pinfunction "GND_16") (pintype "unspecified"))
      (node (ref "USB1") (pin "A1B12") (pinfunction "GND_A1B12") (pintype "unspecified"))
      (node (ref "USB1") (pin "B1A12") (pinfunction "GND_B1A12") (pintype "unspecified"))
    )
    (net (code "14") (name "I2C_ON") (class "Default")
      (node (ref "Q2") (pin "1") (pinfunction "G_1") (pintype "unspecified"))
      (node (ref "R8") (pin "1") (pinfunction "1_1") (pintype "unspecified"))
      (node (ref "R9") (pin "1") (pinfunction "1_1") (pintype "unspecified"))
    )
    (net (code "15") (name "LED_DATA") (class "Default")
      (node (ref "R5") (pin "2") (pinfunction "2_2") (pintype "unspecified"))
      (node (ref "SK6812") (pin "4") (pinfunction "DIN_4") (pintype "unspecified"))
    )
    (net (code "16") (name "LED_ON") (class "Default")
      (node (ref "Q5") (pin "1") (pinfunction "G_1") (pintype "unspecified"))
      (node (ref "R20") (pin "1") (pinfunction "1_1") (pintype "unspecified"))
      (node (ref "R21") (pin "1") (pinfunction "1_1") (pintype "unspecified"))
    )
    (net (code "17") (name "Net-(BUZZER1-Pad1)") (class "Default")
      (node (ref "BUZZER1") (pin "1") (pinfunction "1_1") (pintype "unspecified"))
      (node (ref "R12") (pin "2") (pinfunction "2_2") (pintype "unspecified"))
      (node (ref "R15") (pin "1") (pinfunction "1_1") (pintype "unspecified"))
    )
    (net (code "18") (name "Net-(B_LED1-Pad2)") (class "Default")
      (node (ref "B_LED1") (pin "2") (pinfunction "2_2") (pintype "unspecified"))
      (node (ref "R25") (pin "1") (pinfunction "1_1") (pintype "unspecified"))
    )
    (net (code "19") (name "Net-(C6-Pad1)") (class "Default")
      (node (ref "C6") (pin "1") (pinfunction "1_1") (pintype "unspecified"))
      (node (ref "R14") (pin "2") (pinfunction "2_2") (pintype "unspecified"))
    )
    (net (code "20") (name "Net-(Q5-S)") (class "Default")
      (node (ref "C8") (pin "2") (pinfunction "2_2") (pintype "unspecified"))
      (node (ref "Q5") (pin "2") (pinfunction "S_2") (pintype "unspecified"))
      (node (ref "SK6812") (pin "1") (pinfunction "VDD_1") (pintype "unspecified"))
    )
    (net (code "21") (name "Net-(Q6-D12-Pad2)") (class "Default")
      (node (ref "Q6") (pin "2") (pinfunction "D12_2") (pintype "unspecified"))
      (node (ref "Q6") (pin "5") (pinfunction "D12_5") (pintype "unspecified"))
    )
    (net (code "22") (name "Net-(Q6-G1)") (class "Default")
      (node (ref "Q6") (pin "6") (pinfunction "G1_6") (pintype "unspecified"))
      (node (ref "U4") (pin "3") (pinfunction "OC_3") (pintype "unspecified"))
    )
    (net (code "23") (name "Net-(Q6-G2)") (class "Default")
      (node (ref "Q6") (pin "4") (pinfunction "G2_4") (pintype "unspecified"))
      (node (ref "U4") (pin "1") (pinfunction "OD_1") (pintype "unspecified"))
    )
    (net (code "24") (name "Net-(R26-Pad1)") (class "Default")
      (node (ref "R26") (pin "1") (pinfunction "1_1") (pintype "unspecified"))
      (node (ref "Y_LED2") (pin "2") (pinfunction "2_2") (pintype "unspecified"))
    )
    (net (code "25") (name "Net-(U4-CS)") (class "Default")
      (node (ref "R22") (pin "2") (pinfunction "2_2") (pintype "unspecified"))
      (node (ref "U4") (pin "2") (pinfunction "CS_2") (pintype "unspecified"))
    )
    (net (code "26") (name "Net-(U4-VCC)") (class "Default")
      (node (ref "C7") (pin "2") (pinfunction "2_2") (pintype "unspecified"))
      (node (ref "R23") (pin "1") (pinfunction "1_1") (pintype "input"))
      (node (ref "U4") (pin "5") (pinfunction "VCC_5") (pintype "unspecified"))
    )
    (net (code "27") (name "Net-(USB1-CC1)") (class "Default")
      (node (ref "R2") (pin "1") (pinfunction "1_1") (pintype "unspecified"))
      (node (ref "USB1") (pin "A5") (pinfunction "CC1_A5") (pintype "unspecified"))
    )
    (net (code "28") (name "Net-(USB1-CC2)") (class "Default")
      (node (ref "R1") (pin "1") (pinfunction "1_1") (pintype "unspecified"))
      (node (ref "USB1") (pin "B5") (pinfunction "CC2_B5") (pintype "unspecified"))
    )
    (net (code "29") (name "RXD") (class "Default")
      (node (ref "H1") (pin "2") (pinfunction "2_2") (pintype "unspecified"))
      (node (ref "U2") (pin "11") (pinfunction "RXD_11") (pintype "unspecified"))
    )
    (net (code "30") (name "SCL") (class "Default")
      (node (ref "PIN_EXTRA") (pin "3") (pinfunction "3_3") (pintype "unspecified"))
      (node (ref "PIN_OLED") (pin "3") (pinfunction "3_3") (pintype "unspecified"))
      (node (ref "PIN_SCD") (pin "3") (pinfunction "3_3") (pintype "unspecified"))
      (node (ref "R4") (pin "1") (pinfunction "1_1") (pintype "unspecified"))
      (node (ref "U2") (pin "4") (pinfunction "IO5_4") (pintype "unspecified"))
    )
    (net (code "31") (name "SDA") (class "Default")
      (node (ref "PIN_EXTRA") (pin "4") (pinfunction "4_4") (pintype "unspecified"))
      (node (ref "PIN_OLED") (pin "4") (pinfunction "4_4") (pintype "unspecified"))
      (node (ref "PIN_SCD") (pin "4") (pinfunction "4_4") (pintype "unspecified"))
      (node (ref "R3") (pin "1") (pinfunction "1_1") (pintype "unspecified"))
      (node (ref "U2") (pin "3") (pinfunction "IO4_3") (pintype "unspecified"))
    )
    (net (code "32") (name "TXD") (class "Default")
      (node (ref "H1") (pin "1") (pinfunction "1_1") (pintype "unspecified"))
      (node (ref "U2") (pin "12") (pinfunction "TXD_12") (pintype "unspecified"))
    )
    (net (code "33") (name "VBUS") (class "Default")
      (node (ref "B_LED1") (pin "1") (pinfunction "1_1") (pintype "unspecified"))
      (node (ref "D1") (pin "2") (pinfunction "A_2") (pintype "unspecified"))
      (node (ref "D2") (pin "5") (pinfunction "VBUS_5") (pintype "unspecified"))
      (node (ref "D3") (pin "1") (pinfunction "C_1") (pintype "unspecified"))
      (node (ref "R28") (pin "2") (pinfunction "2_2") (pintype "unspecified"))
      (node (ref "U6") (pin "4") (pinfunction "VCC_4") (pintype "unspecified"))
      (node (ref "U6") (pin "8") (pinfunction "CE_8") (pintype "unspecified"))
      (node (ref "USB1") (pin "A4B9") (pinfunction "VBUS_A4B9") (pintype "unspecified"))
      (node (ref "USB1") (pin "B4A9") (pinfunction "VBUS_B4A9") (pintype "unspecified"))
      (node (ref "Y_LED2") (pin "1") (pinfunction "1_1") (pintype "unspecified"))
    )
    (net (code "34") (name "V_SYS") (class "Default")
      (node (ref "C5") (pin "2") (pinfunction "2_2") (pintype "unspecified"))
      (node (ref "C6") (pin "2") (pinfunction "2_2") (pintype "unspecified"))
      (node (ref "D1") (pin "1") (pinfunction "K_1") (pintype "unspecified"))
      (node (ref "Q1") (pin "1") (pinfunction "G_1") (pintype "unspecified"))
      (node (ref "Q1") (pin "2") (pinfunction "S_2") (pintype "unspecified"))
      (node (ref "Q5") (pin "3") (pinfunction "D_3") (pintype "unspecified"))
      (node (ref "R16") (pin "2") (pinfunction "2_2") (pintype "unspecified"))
      (node (ref "R21") (pin "2") (pinfunction "2_2") (pintype "unspecified"))
      (node (ref "U1") (pin "1") (pinfunction "CE_1") (pintype "unspecified"))
      (node (ref "U1") (pin "4") (pinfunction "VIN_4") (pintype "unspecified"))
    )
    (net (code "35") (name "YLEDR") (class "Default")
      (node (ref "R26") (pin "2") (pinfunction "2_2") (pintype "unspecified"))
      (node (ref "U6") (pin "7") (pinfunction "CHRG#_7") (pintype "unspecified"))
    )
    (net (code "36") (name "boot") (class "Default")
      (node (ref "H2") (pin "1") (pinfunction "1_1") (pintype "unspecified"))
      (node (ref "R6") (pin "2") (pinfunction "2_2") (pintype "unspecified"))
      (node (ref "U2") (pin "8") (pinfunction "IO9_8") (pintype "unspecified"))
    )
    (net (code "37") (name "i2cOnESP") (class "Default")
      (node (ref "R9") (pin "2") (pinfunction "2_2") (pintype "unspecified"))
      (node (ref "U2") (pin "5") (pinfunction "IO6_5") (pintype "unspecified"))
    )
    (net (code "38") (name "inputSW1") (class "Default")
      (node (ref "R11") (pin "1") (pinfunction "1_1") (pintype "unspecified"))
      (node (ref "SW1") (pin "1") (pinfunction "A_1") (pintype "unspecified"))
      (node (ref "SW1") (pin "2") (pinfunction "B_2") (pintype "unspecified"))
      (node (ref "U2") (pin "15") (pinfunction "IO3_15") (pintype "unspecified"))
    )
    (net (code "39") (name "ledDataESP") (class "Default")
      (node (ref "R5") (pin "1") (pinfunction "1_1") (pintype "unspecified"))
      (node (ref "U2") (pin "10") (pinfunction "IO10_10") (pintype "unspecified"))
    )
    (net (code "40") (name "ledOnESP") (class "Default")
      (node (ref "R20") (pin "2") (pinfunction "2_2") (pintype "unspecified"))
      (node (ref "U2") (pin "6") (pinfunction "IO7_6") (pintype "unspecified"))
    )
    (net (code "41") (name "piezo_circ") (class "Default")
      (node (ref "H9") (pin "1") (pinfunction "1_1") (pintype "unspecified"))
      (node (ref "R15") (pin "2") (pinfunction "2_2") (pintype "unspecified"))
      (node (ref "U2") (pin "18") (pinfunction "IO0_18") (pintype "unspecified"))
    )
    (net (code "42") (name "progR") (class "Default")
      (node (ref "R24") (pin "1") (pinfunction "1_1") (pintype "unspecified"))
      (node (ref "U6") (pin "2") (pinfunction "PROG_2") (pintype "unspecified"))
    )
    (net (code "43") (name "temp") (class "Default")
      (node (ref "H8") (pin "1") (pinfunction "1_1") (pintype "unspecified"))
      (node (ref "R27") (pin "2") (pinfunction "2_2") (pintype "unspecified"))
      (node (ref "R28") (pin "1") (pinfunction "1_1") (pintype "unspecified"))
      (node (ref "R29") (pin "2") (pinfunction "2_2") (pintype "input"))
      (node (ref "U6") (pin "1") (pinfunction "TEMP_1") (pintype "unspecified"))
    )
    (net (code "44") (name "unconnected-(SK6812-DOUT-Pad2)") (class "Default")
      (node (ref "SK6812") (pin "2") (pinfunction "DOUT_2") (pintype "unspecified+no_connect"))
    )
    (net (code "45") (name "unconnected-(SWITCH1-Pad1)") (class "Default")
      (node (ref "SWITCH1") (pin "1") (pinfunction "1_1") (pintype "unspecified+no_connect"))
    )
    (net (code "46") (name "unconnected-(SWITCH1-Pad4)") (class "Default")
      (node (ref "SWITCH1") (pin "4") (pinfunction "4_4") (pintype "unspecified+no_connect"))
    )
    (net (code "47") (name "unconnected-(U1-NC-Pad3)") (class "Default")
      (node (ref "U1") (pin "3") (pinfunction "NC_3") (pintype "unspecified+no_connect"))
    )
    (net (code "48") (name "unconnected-(U2-IO2-Pad16)") (class "Default")
      (node (ref "U2") (pin "16") (pinfunction "IO2_16") (pintype "unspecified+no_connect"))
    )
    (net (code "49") (name "unconnected-(U2-IO8-Pad7)") (class "Default")
      (node (ref "U2") (pin "7") (pinfunction "IO8_7") (pintype "unspecified+no_connect"))
    )
    (net (code "50") (name "unconnected-(U4-TD-Pad4)") (class "Default")
      (node (ref "U4") (pin "4") (pinfunction "TD_4") (pintype "unspecified+no_connect"))
    )
    (net (code "51") (name "unconnected-(USB1-SBU1-PadA8)") (class "Default")
      (node (ref "USB1") (pin "A8") (pinfunction "SBU1_A8") (pintype "unspecified+no_connect"))
    )
    (net (code "52") (name "unconnected-(USB1-SBU2-PadB8)") (class "Default")
      (node (ref "USB1") (pin "B8") (pinfunction "SBU2_B8") (pintype "unspecified+no_connect"))
    )
  )
)
